# SDRAM.net
KiCad netlist of a schematic drawn in Altium Designer
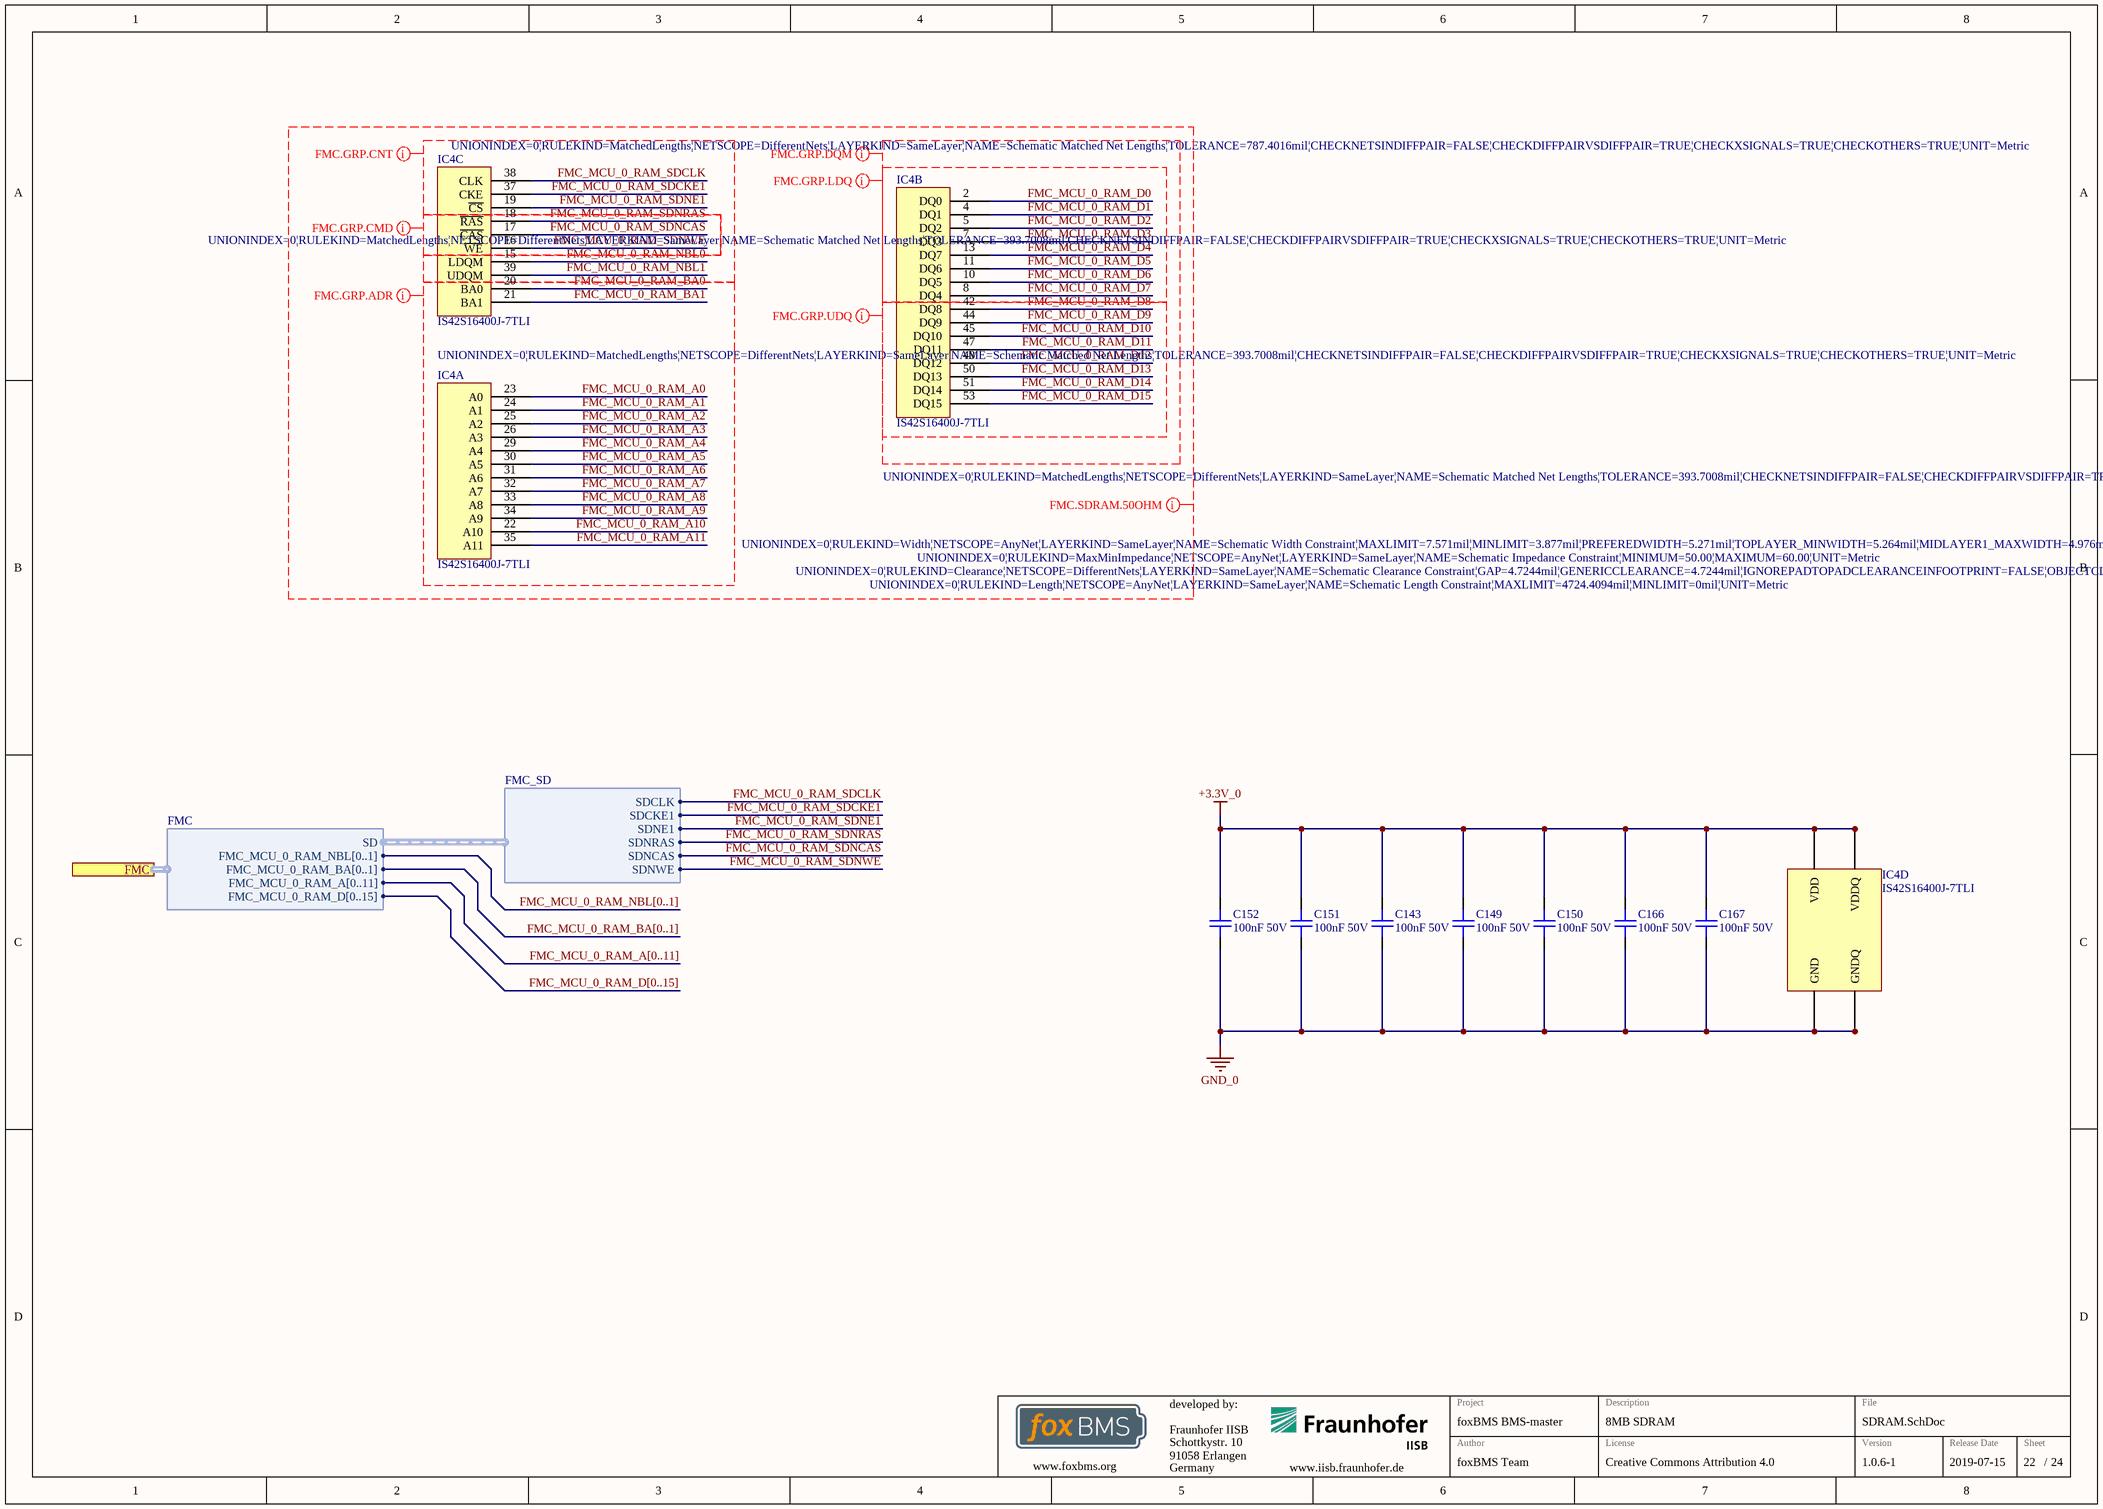
[diagram p0: SDRAM.SchDoc]

(export (version "E")
  (design (tool "Eeschema 10.0.6"))
  (components
    (comp (ref "C143")
      (value "100nF 50V")
      (footprint "0603C")
      (description "Ceramic, 100nF, ±10%, 50V, X7R, –55 to 125°C, 0603 (1608),RoHS, Automotive")
      (fields (field (name "PART NUMBER") "GCJ188R71H104KA12") (field (name "TOLERANCE") "±10%"))
      (libsource (lib "master-010106") (part "C"))
    )
    (comp (ref "C149")
      (value "100nF 50V")
      (footprint "0603C")
      (description "Ceramic, 100nF, ±10%, 50V, X7R, –55 to 125°C, 0603 (1608),RoHS, Automotive")
      (fields (field (name "PART NUMBER") "GCJ188R71H104KA12") (field (name "TOLERANCE") "±10%"))
      (libsource (lib "master-010106") (part "C"))
    )
    (comp (ref "C150")
      (value "100nF 50V")
      (footprint "0603C")
      (description "Ceramic, 100nF, ±10%, 50V, X7R, –55 to 125°C, 0603 (1608),RoHS, Automotive")
      (fields (field (name "PART NUMBER") "GCJ188R71H104KA12") (field (name "TOLERANCE") "±10%"))
      (libsource (lib "master-010106") (part "C"))
    )
    (comp (ref "C151")
      (value "100nF 50V")
      (footprint "0603C")
      (description "Ceramic, 100nF, ±10%, 50V, X7R, –55 to 125°C, 0603 (1608),RoHS, Automotive")
      (fields (field (name "PART NUMBER") "GCJ188R71H104KA12") (field (name "TOLERANCE") "±10%"))
      (libsource (lib "master-010106") (part "C"))
    )
    (comp (ref "C152")
      (value "100nF 50V")
      (footprint "0603C")
      (description "Ceramic, 100nF, ±10%, 50V, X7R, –55 to 125°C, 0603 (1608),RoHS, Automotive")
      (fields (field (name "PART NUMBER") "GCJ188R71H104KA12") (field (name "TOLERANCE") "±10%"))
      (libsource (lib "master-010106") (part "C"))
    )
    (comp (ref "C166")
      (value "100nF 50V")
      (footprint "0603C")
      (description "Ceramic, 100nF, ±10%, 50V, X7R, –55 to 125°C, 0603 (1608),RoHS, Automotive")
      (fields (field (name "PART NUMBER") "GCJ188R71H104KA12") (field (name "TOLERANCE") "±10%"))
      (libsource (lib "master-010106") (part "C"))
    )
    (comp (ref "C167")
      (value "100nF 50V")
      (footprint "0603C")
      (description "Ceramic, 100nF, ±10%, 50V, X7R, –55 to 125°C, 0603 (1608),RoHS, Automotive")
      (fields (field (name "PART NUMBER") "GCJ188R71H104KA12") (field (name "TOLERANCE") "±10%"))
      (libsource (lib "master-010106") (part "C"))
    )
    (comp (ref "IC4")
      (value "IS42S16400J-7TLI")
      (footprint "TSOP80P1180X120-54N")
      (description "SDRAM, 4M x 16 Bit")
      (fields (field (name "MANUFACTURER") "INTEGRATED SILICON SOLUTION (ISSI)"))
      (libsource (lib "OE750") (part "IS42S16400J-7TLI"))
    )
  )
  (nets
    (net (code "3") (name "+3.3V_0") (class "Default")
      (node (ref "C143") (pin "1") (pinfunction "1_1") (pintype "passive"))
      (node (ref "C149") (pin "1") (pinfunction "1_1") (pintype "passive"))
      (node (ref "C150") (pin "1") (pinfunction "1_1") (pintype "passive"))
      (node (ref "C151") (pin "1") (pinfunction "1_1") (pintype "passive"))
      (node (ref "C152") (pin "1") (pinfunction "1_1") (pintype "passive"))
      (node (ref "C166") (pin "1") (pinfunction "1_1") (pintype "passive"))
      (node (ref "C167") (pin "1") (pinfunction "1_1") (pintype "passive"))
      (node (ref "IC4") (pin "1") (pinfunction "VDD_1") (pintype "power_in"))
      (node (ref "IC4") (pin "14") (pinfunction "VDD_14") (pintype "power_in"))
      (node (ref "IC4") (pin "27") (pinfunction "VDD_27") (pintype "power_in"))
      (node (ref "IC4") (pin "3") (pinfunction "VDDQ_3") (pintype "power_in"))
      (node (ref "IC4") (pin "43") (pinfunction "VDDQ_43") (pintype "power_in"))
      (node (ref "IC4") (pin "49") (pinfunction "VDDQ_49") (pintype "power_in"))
      (node (ref "IC4") (pin "9") (pinfunction "VDDQ_9") (pintype "power_in"))
    )
    (net (code "4") (name "/FMC_MCU_0_RAM_A0") (class "Default")
      (node (ref "IC4") (pin "23") (pinfunction "A0_23") (pintype "passive"))
    )
    (net (code "5") (name "/FMC_MCU_0_RAM_A1") (class "Default")
      (node (ref "IC4") (pin "24") (pinfunction "A1_24") (pintype "passive"))
    )
    (net (code "6") (name "/FMC_MCU_0_RAM_A2") (class "Default")
      (node (ref "IC4") (pin "25") (pinfunction "A2_25") (pintype "passive"))
    )
    (net (code "7") (name "/FMC_MCU_0_RAM_A3") (class "Default")
      (node (ref "IC4") (pin "26") (pinfunction "A3_26") (pintype "passive"))
    )
    (net (code "8") (name "/FMC_MCU_0_RAM_A4") (class "Default")
      (node (ref "IC4") (pin "29") (pinfunction "A4_29") (pintype "passive"))
    )
    (net (code "9") (name "/FMC_MCU_0_RAM_A5") (class "Default")
      (node (ref "IC4") (pin "30") (pinfunction "A5_30") (pintype "passive"))
    )
    (net (code "10") (name "/FMC_MCU_0_RAM_A6") (class "Default")
      (node (ref "IC4") (pin "31") (pinfunction "A6_31") (pintype "passive"))
    )
    (net (code "11") (name "/FMC_MCU_0_RAM_A7") (class "Default")
      (node (ref "IC4") (pin "32") (pinfunction "A7_32") (pintype "passive"))
    )
    (net (code "12") (name "/FMC_MCU_0_RAM_A8") (class "Default")
      (node (ref "IC4") (pin "33") (pinfunction "A8_33") (pintype "passive"))
    )
    (net (code "13") (name "/FMC_MCU_0_RAM_A9") (class "Default")
      (node (ref "IC4") (pin "34") (pinfunction "A9_34") (pintype "passive"))
    )
    (net (code "14") (name "/FMC_MCU_0_RAM_A10") (class "Default")
      (node (ref "IC4") (pin "22") (pinfunction "A10_22") (pintype "passive"))
    )
    (net (code "15") (name "/FMC_MCU_0_RAM_A11") (class "Default")
      (node (ref "IC4") (pin "35") (pinfunction "A11_35") (pintype "passive"))
    )
    (net (code "17") (name "/FMC_MCU_0_RAM_BA0") (class "Default")
      (node (ref "IC4") (pin "20") (pinfunction "BA0_20") (pintype "passive"))
    )
    (net (code "18") (name "/FMC_MCU_0_RAM_BA1") (class "Default")
      (node (ref "IC4") (pin "21") (pinfunction "BA1_21") (pintype "passive"))
    )
    (net (code "20") (name "/FMC_MCU_0_RAM_D0") (class "Default")
      (node (ref "IC4") (pin "2") (pinfunction "DQ0_2") (pintype "passive"))
    )
    (net (code "21") (name "/FMC_MCU_0_RAM_D1") (class "Default")
      (node (ref "IC4") (pin "4") (pinfunction "DQ1_4") (pintype "passive"))
    )
    (net (code "22") (name "/FMC_MCU_0_RAM_D2") (class "Default")
      (node (ref "IC4") (pin "5") (pinfunction "DQ2_5") (pintype "passive"))
    )
    (net (code "23") (name "/FMC_MCU_0_RAM_D3") (class "Default")
      (node (ref "IC4") (pin "7") (pinfunction "DQ3_7") (pintype "passive"))
    )
    (net (code "24") (name "/FMC_MCU_0_RAM_D4") (class "Default")
      (node (ref "IC4") (pin "13") (pinfunction "DQ7_13") (pintype "passive"))
    )
    (net (code "25") (name "/FMC_MCU_0_RAM_D5") (class "Default")
      (node (ref "IC4") (pin "11") (pinfunction "DQ6_11") (pintype "passive"))
    )
    (net (code "26") (name "/FMC_MCU_0_RAM_D6") (class "Default")
      (node (ref "IC4") (pin "10") (pinfunction "DQ5_10") (pintype "passive"))
    )
    (net (code "27") (name "/FMC_MCU_0_RAM_D7") (class "Default")
      (node (ref "IC4") (pin "8") (pinfunction "DQ4_8") (pintype "passive"))
    )
    (net (code "28") (name "/FMC_MCU_0_RAM_D8") (class "Default")
      (node (ref "IC4") (pin "42") (pinfunction "DQ8_42") (pintype "passive"))
    )
    (net (code "29") (name "/FMC_MCU_0_RAM_D9") (class "Default")
      (node (ref "IC4") (pin "44") (pinfunction "DQ9_44") (pintype "passive"))
    )
    (net (code "30") (name "/FMC_MCU_0_RAM_D10") (class "Default")
      (node (ref "IC4") (pin "45") (pinfunction "DQ10_45") (pintype "passive"))
    )
    (net (code "31") (name "/FMC_MCU_0_RAM_D11") (class "Default")
      (node (ref "IC4") (pin "47") (pinfunction "DQ11_47") (pintype "passive"))
    )
    (net (code "32") (name "/FMC_MCU_0_RAM_D12") (class "Default")
      (node (ref "IC4") (pin "48") (pinfunction "DQ12_48") (pintype "passive"))
    )
    (net (code "33") (name "/FMC_MCU_0_RAM_D13") (class "Default")
      (node (ref "IC4") (pin "50") (pinfunction "DQ13_50") (pintype "passive"))
    )
    (net (code "34") (name "/FMC_MCU_0_RAM_D14") (class "Default")
      (node (ref "IC4") (pin "51") (pinfunction "DQ14_51") (pintype "passive"))
    )
    (net (code "35") (name "/FMC_MCU_0_RAM_D15") (class "Default")
      (node (ref "IC4") (pin "53") (pinfunction "DQ15_53") (pintype "passive"))
    )
    (net (code "37") (name "/FMC_MCU_0_RAM_NBL0") (class "Default")
      (node (ref "IC4") (pin "15") (pinfunction "LDQM_15") (pintype "passive"))
    )
    (net (code "38") (name "/FMC_MCU_0_RAM_NBL1") (class "Default")
      (node (ref "IC4") (pin "39") (pinfunction "UDQM_39") (pintype "passive"))
    )
    (net (code "40") (name "/FMC_MCU_0_RAM_SDCKE1") (class "Default")
      (node (ref "IC4") (pin "37") (pinfunction "CKE_37") (pintype "passive"))
    )
    (net (code "41") (name "/FMC_MCU_0_RAM_SDCLK") (class "Default")
      (node (ref "IC4") (pin "38") (pinfunction "CLK_38") (pintype "passive"))
    )
    (net (code "42") (name "/FMC_MCU_0_RAM_SDNCAS") (class "Default")
      (node (ref "IC4") (pin "17") (pinfunction "~{CAS}_17") (pintype "passive"))
    )
    (net (code "43") (name "/FMC_MCU_0_RAM_SDNE1") (class "Default")
      (node (ref "IC4") (pin "19") (pinfunction "~{CS}_19") (pintype "passive"))
    )
    (net (code "44") (name "/FMC_MCU_0_RAM_SDNRAS") (class "Default")
      (node (ref "IC4") (pin "18") (pinfunction "~{RAS}_18") (pintype "passive"))
    )
    (net (code "45") (name "/FMC_MCU_0_RAM_SDNWE") (class "Default")
      (node (ref "IC4") (pin "16") (pinfunction "~{WE}_16") (pintype "passive"))
    )
    (net (code "48") (name "GND_0") (class "Default")
      (node (ref "C143") (pin "2") (pinfunction "2_2") (pintype "passive"))
      (node (ref "C149") (pin "2") (pinfunction "2_2") (pintype "passive"))
      (node (ref "C150") (pin "2") (pinfunction "2_2") (pintype "passive"))
      (node (ref "C151") (pin "2") (pinfunction "2_2") (pintype "passive"))
      (node (ref "C152") (pin "2") (pinfunction "2_2") (pintype "passive"))
      (node (ref "C166") (pin "2") (pinfunction "2_2") (pintype "passive"))
      (node (ref "C167") (pin "2") (pinfunction "2_2") (pintype "passive"))
      (node (ref "IC4") (pin "12") (pinfunction "GNDQ_12") (pintype "power_in"))
      (node (ref "IC4") (pin "28") (pinfunction "GND_28") (pintype "power_in"))
      (node (ref "IC4") (pin "41") (pinfunction "GND_41") (pintype "power_in"))
      (node (ref "IC4") (pin "46") (pinfunction "GNDQ_46") (pintype "power_in"))
      (node (ref "IC4") (pin "52") (pinfunction "GNDQ_52") (pintype "power_in"))
      (node (ref "IC4") (pin "54") (pinfunction "GND_54") (pintype "power_in"))
      (node (ref "IC4") (pin "6") (pinfunction "GNDQ_6") (pintype "power_in"))
    )
  )
)
